# RGB_CA_v1_0.net
KiCad netlist of a schematic drawn in Altium Designer
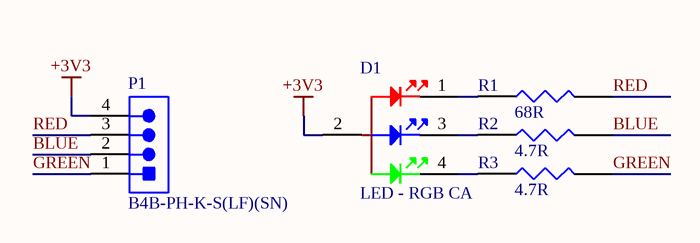
[diagram p0: RGB_CA_v1.0.SchDoc]

(export (version "E")
  (design (tool "Eeschema 10.0.6"))
  (components
    (comp (ref "D1")
      (value "LED - RGB CA")
      (footprint "LED RGB CA 3528")
      (description "Multicolor LED Red/Green/Blue 624nm/535nm/475nm 50mA/25mA/25mA 4-Pin SMD T/R")
      (fields
        (field (name "MANUFACTURER") "Cree")
        (field (name "MANUFACTURER PART NUMBER") "CLV1A-FKB-CK1VW1DE1BB7C3C3")
      )
      (libsource (lib "Limit_Switch_RGB") (part "CLV1A-FKB-CK1VW1DE1BB7C3C3"))
    )
    (comp (ref "P1")
      (value "B4B-PH-K-S(LF)(SN)")
      (footprint "JST-B4B-PH-K-S_V")
      (fields (field (name "MANUFACTURER") "JST"))
      (libsource (lib "Altium Content Vault") (part "CN-1P-M-R4"))
    )
    (comp (ref "R1")
      (value "68R")
      (footprint "68R 0603")
      (description "CRGP 0603 68R 1%")
      (fields
        (field (name "MANUFACTURER") "TE Connectivity")
        (field (name "MANUFACTURER PART NUMBER") "CRGP0603F68R")
      )
      (libsource (lib "Limit_Switch_RGB") (part "CRGP0603F68R"))
    )
    (comp (ref "R2")
      (value "4.7R")
      (footprint "4.7R 0603")
      (fields
        (field (name "MANUFACTURER") "TE Connectivity")
        (field (name "MANUFACTURER PART NUMBER") "CRGCQ0603J4R7")
      )
      (libsource (lib "Limit_Switch_RGB") (part "CRGCQ0603J4R7"))
    )
    (comp (ref "R3")
      (value "4.7R")
      (footprint "4.7R 0603")
      (fields
        (field (name "MANUFACTURER") "TE Connectivity")
        (field (name "MANUFACTURER PART NUMBER") "CRGCQ0603J4R7")
      )
      (libsource (lib "Limit_Switch_RGB") (part "CRGCQ0603J4R7"))
    )
  )
  (nets
    (net (code "1") (name "+3V3") (class "Default")
      (node (ref "D1") (pin "2") (pinfunction "Anode_2") (pintype "passive"))
      (node (ref "P1") (pin "4") (pinfunction "4_4") (pintype "passive"))
    )
    (net (code "2") (name "/BLUE") (class "Default")
      (node (ref "P1") (pin "2") (pinfunction "2_2") (pintype "passive"))
      (node (ref "R2") (pin "2") (pinfunction "2_2") (pintype "passive"))
    )
    (net (code "3") (name "/GREEN") (class "Default")
      (node (ref "P1") (pin "1") (pinfunction "1_1") (pintype "passive"))
      (node (ref "R3") (pin "2") (pinfunction "2_2") (pintype "passive"))
    )
    (net (code "4") (name "/RED") (class "Default")
      (node (ref "P1") (pin "3") (pinfunction "3_3") (pintype "passive"))
      (node (ref "R1") (pin "2") (pinfunction "2_2") (pintype "passive"))
    )
    (net (code "5") (name "Net-(D1-Blue)") (class "Default")
      (node (ref "D1") (pin "3") (pinfunction "Blue_3") (pintype "passive"))
      (node (ref "R2") (pin "1") (pinfunction "1_1") (pintype "passive"))
    )
    (net (code "6") (name "Net-(D1-Green)") (class "Default")
      (node (ref "D1") (pin "4") (pinfunction "Green_4") (pintype "passive"))
      (node (ref "R3") (pin "1") (pinfunction "1_1") (pintype "passive"))
    )
    (net (code "7") (name "Net-(D1-Red)") (class "Default")
      (node (ref "D1") (pin "1") (pinfunction "Red_1") (pintype "passive"))
      (node (ref "R1") (pin "1") (pinfunction "1_1") (pintype "passive"))
    )
  )
)
